# Hocki-IR-Receiver.net
KiCad netlist of a schematic drawn in EAGLE
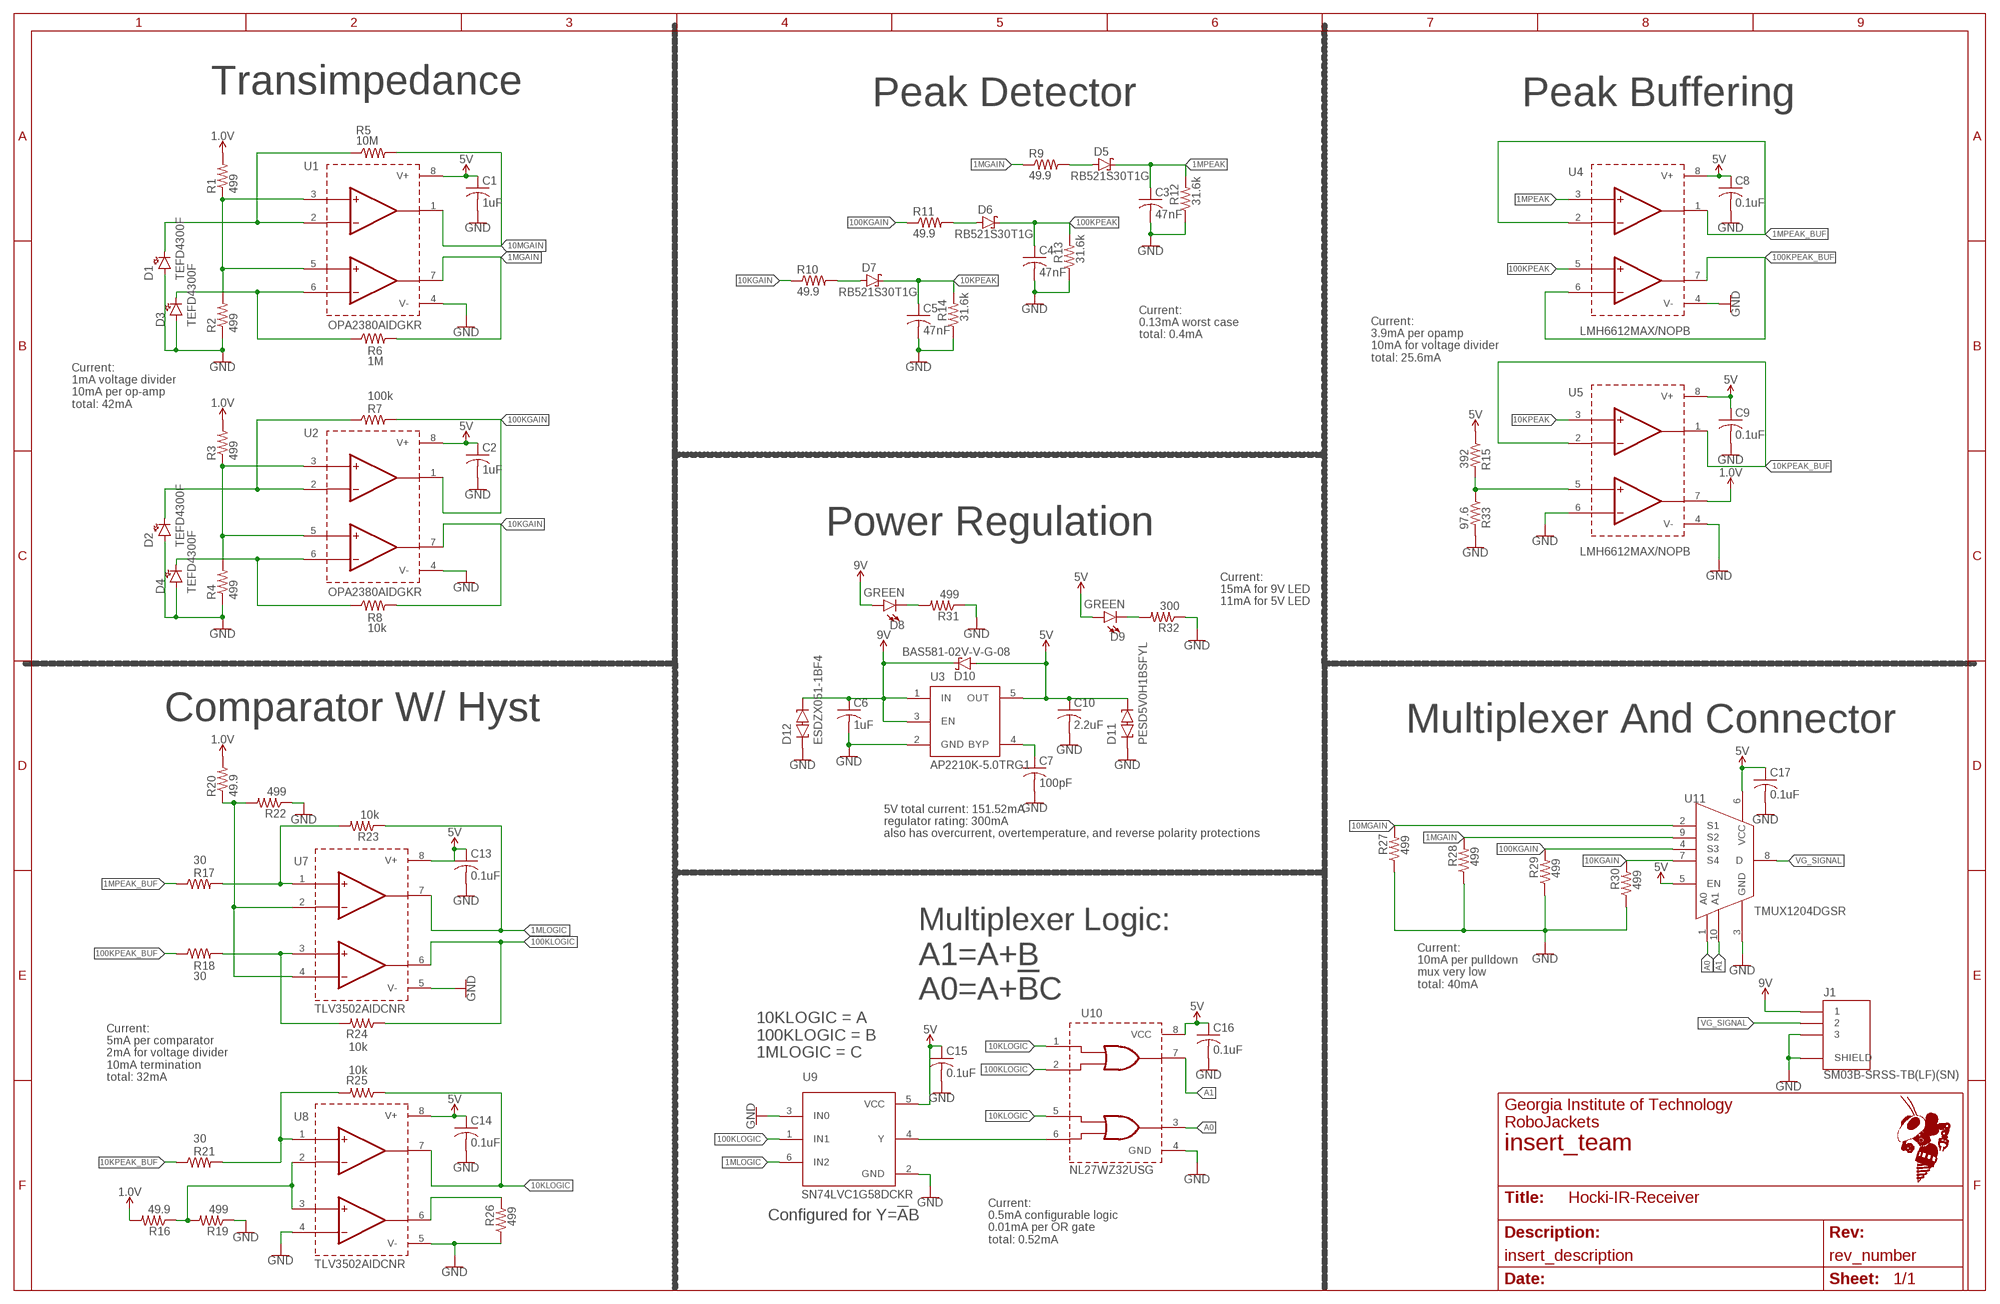
[diagram p0: schematic, sheet 1]

(export (version "E")
  (design (tool "Eeschema 10.0.6"))
  (components
    (comp (ref "C1")
      (value "1uF")
      (footprint "eagle-import:C0603")
      (libsource (lib "eagle-import") (part "C-USC0603"))
    )
    (comp (ref "C2")
      (value "1uF")
      (footprint "eagle-import:C0603")
      (libsource (lib "eagle-import") (part "C-USC0603"))
    )
    (comp (ref "C3")
      (value "47nF")
      (footprint "eagle-import:C1206")
      (libsource (lib "eagle-import") (part "C-USC1206"))
    )
    (comp (ref "C4")
      (value "47nF")
      (footprint "eagle-import:C1206")
      (libsource (lib "eagle-import") (part "C-USC1206"))
    )
    (comp (ref "C5")
      (value "47nF")
      (footprint "eagle-import:C1206")
      (libsource (lib "eagle-import") (part "C-USC1206"))
    )
    (comp (ref "C6")
      (value "1uF")
      (footprint "eagle-import:C0603")
      (libsource (lib "eagle-import") (part "C-USC0603"))
    )
    (comp (ref "C7")
      (value "100pF")
      (footprint "eagle-import:C0603")
      (libsource (lib "eagle-import") (part "C-USC0603"))
    )
    (comp (ref "C8")
      (value "0.1uF")
      (footprint "eagle-import:C0603")
      (libsource (lib "eagle-import") (part "C-USC0603"))
    )
    (comp (ref "C9")
      (value "0.1uF")
      (footprint "eagle-import:C0603")
      (libsource (lib "eagle-import") (part "C-USC0603"))
    )
    (comp (ref "C10")
      (value "2.2uF")
      (footprint "eagle-import:C0603")
      (libsource (lib "eagle-import") (part "C-USC0603"))
    )
    (comp (ref "C13")
      (value "0.1uF")
      (footprint "eagle-import:C0603")
      (libsource (lib "eagle-import") (part "C-USC0603"))
    )
    (comp (ref "C14")
      (value "0.1uF")
      (footprint "eagle-import:C0603")
      (libsource (lib "eagle-import") (part "C-USC0603"))
    )
    (comp (ref "C15")
      (value "0.1uF")
      (footprint "eagle-import:C0603")
      (libsource (lib "eagle-import") (part "C-USC0603"))
    )
    (comp (ref "C16")
      (value "0.1uF")
      (footprint "eagle-import:C0603")
      (libsource (lib "eagle-import") (part "C-USC0603"))
    )
    (comp (ref "C17")
      (value "0.1uF")
      (footprint "eagle-import:C0603")
      (libsource (lib "eagle-import") (part "C-USC0603"))
    )
    (comp (ref "D1")
      (value "TEFD4300F")
      (footprint "eagle-import:TEFD4300F")
      (libsource (lib "eagle-import") (part "TEFD4300F"))
    )
    (comp (ref "D2")
      (value "TEFD4300F")
      (footprint "eagle-import:TEFD4300F")
      (libsource (lib "eagle-import") (part "TEFD4300F"))
    )
    (comp (ref "D3")
      (value "TEFD4300F")
      (footprint "eagle-import:TEFD4300F")
      (libsource (lib "eagle-import") (part "TEFD4300F"))
    )
    (comp (ref "D4")
      (value "TEFD4300F")
      (footprint "eagle-import:TEFD4300F")
      (libsource (lib "eagle-import") (part "TEFD4300F"))
    )
    (comp (ref "D5")
      (value "RB521S30T1G")
      (footprint "eagle-import:SOD-523")
      (libsource (lib "eagle-import") (part "RB521S30T1G"))
    )
    (comp (ref "D6")
      (value "RB521S30T1G")
      (footprint "eagle-import:SOD-523")
      (libsource (lib "eagle-import") (part "RB521S30T1G"))
    )
    (comp (ref "D7")
      (value "RB521S30T1G")
      (footprint "eagle-import:SOD-523")
      (libsource (lib "eagle-import") (part "RB521S30T1G"))
    )
    (comp (ref "D8")
      (value "GREEN")
      (footprint "eagle-import:LED-0603")
      (libsource (lib "eagle-import") (part "LED-GREEN0603"))
    )
    (comp (ref "D9")
      (value "GREEN")
      (footprint "eagle-import:LED-0603")
      (libsource (lib "eagle-import") (part "LED-GREEN0603"))
    )
    (comp (ref "D10")
      (value "BAS581-02V-V-G-08")
      (footprint "eagle-import:SOD-523")
      (libsource (lib "eagle-import") (part "BAS581-02V-V-G-08"))
    )
    (comp (ref "D11")
      (value "PESD5V0H1BSFYL")
      (footprint "eagle-import:DSN0603-2")
      (libsource (lib "eagle-import") (part "PESD5V0H1BSFYL"))
    )
    (comp (ref "D12")
      (value "ESDZX051-1BF4")
      (footprint "eagle-import:DSN0603-2")
      (libsource (lib "eagle-import") (part "ESDZX051-1BF4"))
    )
    (comp (ref "J1")
      (value "SM03B-SRSS-TB(LF)(SN)")
      (footprint "eagle-import:SM03B-SRSS-TB(LF)(SN)")
      (libsource (lib "eagle-import") (part "SM03B-SRSS-TB(LF)(SN)"))
    )
    (comp (ref "R1")
      (value "499")
      (footprint "eagle-import:R0603")
      (libsource (lib "eagle-import") (part "resistor_348_R-US_R0603"))
    )
    (comp (ref "R2")
      (value "499")
      (footprint "eagle-import:R0603")
      (libsource (lib "eagle-import") (part "resistor_348_R-US_R0603"))
    )
    (comp (ref "R3")
      (value "499")
      (footprint "eagle-import:R0603")
      (libsource (lib "eagle-import") (part "resistor_348_R-US_R0603"))
    )
    (comp (ref "R4")
      (value "499")
      (footprint "eagle-import:R0603")
      (libsource (lib "eagle-import") (part "resistor_348_R-US_R0603"))
    )
    (comp (ref "R5")
      (value "10M")
      (footprint "eagle-import:R1206")
      (libsource (lib "eagle-import") (part "R-US_R1206"))
    )
    (comp (ref "R6")
      (value "1M")
      (footprint "eagle-import:R0603")
      (libsource (lib "eagle-import") (part "resistor_348_R-US_R0603"))
    )
    (comp (ref "R7")
      (value "100k")
      (footprint "eagle-import:R0603")
      (libsource (lib "eagle-import") (part "resistor_348_R-US_R0603"))
    )
    (comp (ref "R8")
      (value "10k")
      (footprint "eagle-import:R0603")
      (libsource (lib "eagle-import") (part "resistor_348_R-US_R0603"))
    )
    (comp (ref "R9")
      (value "49.9")
      (footprint "eagle-import:R0603")
      (libsource (lib "eagle-import") (part "resistor_348_R-US_R0603"))
    )
    (comp (ref "R10")
      (value "49.9")
      (footprint "eagle-import:R0603")
      (libsource (lib "eagle-import") (part "resistor_348_R-US_R0603"))
    )
    (comp (ref "R11")
      (value "49.9")
      (footprint "eagle-import:R0603")
      (libsource (lib "eagle-import") (part "resistor_348_R-US_R0603"))
    )
    (comp (ref "R12")
      (value "31.6k")
      (footprint "eagle-import:R0603")
      (libsource (lib "eagle-import") (part "resistor_348_R-US_R0603"))
    )
    (comp (ref "R13")
      (value "31.6k")
      (footprint "eagle-import:R0603")
      (libsource (lib "eagle-import") (part "resistor_348_R-US_R0603"))
    )
    (comp (ref "R14")
      (value "31.6k")
      (footprint "eagle-import:R0603")
      (libsource (lib "eagle-import") (part "resistor_348_R-US_R0603"))
    )
    (comp (ref "R15")
      (value "392")
      (footprint "eagle-import:R0603")
      (libsource (lib "eagle-import") (part "resistor_348_R-US_R0603"))
    )
    (comp (ref "R16")
      (value "49.9")
      (footprint "eagle-import:R0603")
      (libsource (lib "eagle-import") (part "resistor_348_R-US_R0603"))
    )
    (comp (ref "R17")
      (value "30")
      (footprint "eagle-import:R0603")
      (libsource (lib "eagle-import") (part "resistor_348_R-US_R0603"))
    )
    (comp (ref "R18")
      (value "30")
      (footprint "eagle-import:R0603")
      (libsource (lib "eagle-import") (part "resistor_348_R-US_R0603"))
    )
    (comp (ref "R19")
      (value "499")
      (footprint "eagle-import:R0603")
      (libsource (lib "eagle-import") (part "resistor_348_R-US_R0603"))
    )
    (comp (ref "R20")
      (value "49.9")
      (footprint "eagle-import:R0603")
      (libsource (lib "eagle-import") (part "resistor_348_R-US_R0603"))
    )
    (comp (ref "R21")
      (value "30")
      (footprint "eagle-import:R0603")
      (libsource (lib "eagle-import") (part "resistor_348_R-US_R0603"))
    )
    (comp (ref "R22")
      (value "499")
      (footprint "eagle-import:R0603")
      (libsource (lib "eagle-import") (part "resistor_348_R-US_R0603"))
    )
    (comp (ref "R23")
      (value "10k")
      (footprint "eagle-import:R0603")
      (libsource (lib "eagle-import") (part "resistor_348_R-US_R0603"))
    )
    (comp (ref "R24")
      (value "10k")
      (footprint "eagle-import:R0603")
      (libsource (lib "eagle-import") (part "resistor_348_R-US_R0603"))
    )
    (comp (ref "R25")
      (value "10k")
      (footprint "eagle-import:R0603")
      (libsource (lib "eagle-import") (part "resistor_348_R-US_R0603"))
    )
    (comp (ref "R26")
      (value "499")
      (footprint "eagle-import:R0603")
      (libsource (lib "eagle-import") (part "resistor_348_R-US_R0603"))
    )
    (comp (ref "R27")
      (value "499")
      (footprint "eagle-import:R0603")
      (libsource (lib "eagle-import") (part "resistor_348_R-US_R0603"))
    )
    (comp (ref "R28")
      (value "499")
      (footprint "eagle-import:R0603")
      (libsource (lib "eagle-import") (part "resistor_348_R-US_R0603"))
    )
    (comp (ref "R29")
      (value "499")
      (footprint "eagle-import:R0603")
      (libsource (lib "eagle-import") (part "resistor_348_R-US_R0603"))
    )
    (comp (ref "R30")
      (value "499")
      (footprint "eagle-import:R0603")
      (libsource (lib "eagle-import") (part "resistor_348_R-US_R0603"))
    )
    (comp (ref "R31")
      (value "499")
      (footprint "eagle-import:R0603")
      (libsource (lib "eagle-import") (part "resistor_348_R-US_R0603"))
    )
    (comp (ref "R32")
      (value "300")
      (footprint "eagle-import:R0603")
      (libsource (lib "eagle-import") (part "resistor_348_R-US_R0603"))
    )
    (comp (ref "R33")
      (value "97.6")
      (footprint "eagle-import:R0603")
      (libsource (lib "eagle-import") (part "resistor_348_R-US_R0603"))
    )
    (comp (ref "U1")
      (value "OPA2380AIDGKR")
      (footprint "eagle-import:8-VSSOP")
      (libsource (lib "eagle-import") (part "OPA2380AIDGKR"))
    )
    (comp (ref "U2")
      (value "OPA2380AIDGKR")
      (footprint "eagle-import:8-VSSOP")
      (libsource (lib "eagle-import") (part "OPA2380AIDGKR"))
    )
    (comp (ref "U3")
      (value "AP2210K-5.0TRG1")
      (footprint "eagle-import:SOT-23-5")
      (libsource (lib "eagle-import") (part "AP2210K-TRG15.0"))
    )
    (comp (ref "U4")
      (value "LMH6612MAX/NOPB")
      (footprint "eagle-import:8-SOIC")
      (libsource (lib "eagle-import") (part "LMH6612MAX/NOPB"))
    )
    (comp (ref "U5")
      (value "LMH6612MAX/NOPB")
      (footprint "eagle-import:8-SOIC")
      (libsource (lib "eagle-import") (part "LMH6612MAX/NOPB"))
    )
    (comp (ref "U7")
      (value "TLV3502AIDCNR")
      (footprint "eagle-import:SOT-23-8")
      (libsource (lib "eagle-import") (part "TLV3502AIDCNR"))
    )
    (comp (ref "U8")
      (value "TLV3502AIDCNR")
      (footprint "eagle-import:SOT-23-8")
      (libsource (lib "eagle-import") (part "TLV3502AIDCNR"))
    )
    (comp (ref "U9")
      (value "SN74LVC1G58DCKR")
      (footprint "eagle-import:SC-70-6")
      (libsource (lib "eagle-import") (part "SN74LVC1G58DCKR"))
    )
    (comp (ref "U10")
      (value "NL27WZ32USG")
      (footprint "eagle-import:US8")
      (libsource (lib "eagle-import") (part "NL27WZ32USG"))
    )
    (comp (ref "U11")
      (value "TMUX1204DGSR")
      (footprint "eagle-import:10-VSSOP")
      (libsource (lib "eagle-import") (part "TMUX1204DGSR"))
    )
  )
  (nets
    (net (code "1") (name "1.0V") (class "Default")
      (node (ref "R1") (pin "2") (pinfunction "2_2") (pintype "passive"))
      (node (ref "R16") (pin "2") (pinfunction "2_2") (pintype "passive"))
      (node (ref "R20") (pin "2") (pinfunction "2_2") (pintype "passive"))
      (node (ref "R3") (pin "2") (pinfunction "2_2") (pintype "passive"))
      (node (ref "U5") (pin "7") (pinfunction "OUTB_7") (pintype "passive"))
    )
    (net (code "2") (name "1MGAIN") (class "Default")
      (node (ref "R28") (pin "2") (pinfunction "2_2") (pintype "passive"))
      (node (ref "R6") (pin "2") (pinfunction "2_2") (pintype "passive"))
      (node (ref "R9") (pin "1") (pinfunction "1_1") (pintype "passive"))
      (node (ref "U1") (pin "7") (pinfunction "OUTB_7") (pintype "passive"))
      (node (ref "U11") (pin "9") (pinfunction "S2_9") (pintype "passive"))
    )
    (net (code "3") (name "1MLOGIC") (class "Default")
      (node (ref "R23") (pin "1") (pinfunction "1_1") (pintype "passive"))
      (node (ref "U7") (pin "7") (pinfunction "OUTA_7") (pintype "passive"))
      (node (ref "U9") (pin "6") (pinfunction "IN2_6") (pintype "passive"))
    )
    (net (code "4") (name "1MPEAK") (class "Default")
      (node (ref "C3") (pin "1") (pinfunction "1_1") (pintype "passive"))
      (node (ref "D5") (pin "1") (pinfunction "C_1") (pintype "passive"))
      (node (ref "R12") (pin "2") (pinfunction "2_2") (pintype "passive"))
      (node (ref "U4") (pin "3") (pinfunction "INA+_3") (pintype "passive"))
    )
    (net (code "5") (name "1MPEAK_BUF") (class "Default")
      (node (ref "R17") (pin "1") (pinfunction "1_1") (pintype "passive"))
      (node (ref "U4") (pin "1") (pinfunction "OUTA_1") (pintype "passive"))
      (node (ref "U4") (pin "2") (pinfunction "INA-_2") (pintype "passive"))
    )
    (net (code "6") (name "5V") (class "Default")
      (node (ref "C1") (pin "1") (pinfunction "1_1") (pintype "passive"))
      (node (ref "C10") (pin "1") (pinfunction "1_1") (pintype "passive"))
      (node (ref "C13") (pin "1") (pinfunction "1_1") (pintype "passive"))
      (node (ref "C14") (pin "1") (pinfunction "1_1") (pintype "passive"))
      (node (ref "C15") (pin "1") (pinfunction "1_1") (pintype "passive"))
      (node (ref "C16") (pin "1") (pinfunction "1_1") (pintype "passive"))
      (node (ref "C17") (pin "1") (pinfunction "1_1") (pintype "passive"))
      (node (ref "C2") (pin "1") (pinfunction "1_1") (pintype "passive"))
      (node (ref "C8") (pin "1") (pinfunction "1_1") (pintype "passive"))
      (node (ref "C9") (pin "1") (pinfunction "1_1") (pintype "passive"))
      (node (ref "D10") (pin "2") (pinfunction "A_2") (pintype "passive"))
      (node (ref "D11") (pin "C2") (pinfunction "C2_C2") (pintype "passive"))
      (node (ref "D9") (pin "A") (pinfunction "A_A") (pintype "passive"))
      (node (ref "R15") (pin "1") (pinfunction "1_1") (pintype "passive"))
      (node (ref "U1") (pin "8") (pinfunction "V+_8") (pintype "passive"))
      (node (ref "U10") (pin "8") (pinfunction "VCC_8") (pintype "passive"))
      (node (ref "U11") (pin "5") (pinfunction "EN_5") (pintype "passive"))
      (node (ref "U11") (pin "6") (pinfunction "VCC_6") (pintype "passive"))
      (node (ref "U2") (pin "8") (pinfunction "V+_8") (pintype "passive"))
      (node (ref "U3") (pin "5") (pinfunction "OUT_5") (pintype "passive"))
      (node (ref "U4") (pin "8") (pinfunction "V+_8") (pintype "passive"))
      (node (ref "U5") (pin "8") (pinfunction "V+_8") (pintype "passive"))
      (node (ref "U7") (pin "8") (pinfunction "V+_8") (pintype "passive"))
      (node (ref "U8") (pin "8") (pinfunction "V+_8") (pintype "passive"))
      (node (ref "U9") (pin "5") (pinfunction "VCC_5") (pintype "passive"))
    )
    (net (code "7") (name "9V") (class "Default")
      (node (ref "C6") (pin "1") (pinfunction "1_1") (pintype "passive"))
      (node (ref "D10") (pin "1") (pinfunction "C_1") (pintype "passive"))
      (node (ref "D12") (pin "C2") (pinfunction "C2_C2") (pintype "passive"))
      (node (ref "D8") (pin "A") (pinfunction "A_A") (pintype "passive"))
      (node (ref "J1") (pin "1") (pinfunction "1_1") (pintype "passive"))
      (node (ref "U3") (pin "1") (pinfunction "IN_1") (pintype "passive"))
      (node (ref "U3") (pin "3") (pinfunction "EN_3") (pintype "passive"))
    )
    (net (code "8") (name "10KGAIN") (class "Default")
      (node (ref "R10") (pin "1") (pinfunction "1_1") (pintype "passive"))
      (node (ref "R30") (pin "2") (pinfunction "2_2") (pintype "passive"))
      (node (ref "R8") (pin "2") (pinfunction "2_2") (pintype "passive"))
      (node (ref "U11") (pin "7") (pinfunction "S4_7") (pintype "passive"))
      (node (ref "U2") (pin "7") (pinfunction "OUTB_7") (pintype "passive"))
    )
    (net (code "9") (name "10KLOGIC") (class "Default")
      (node (ref "R25") (pin "1") (pinfunction "1_1") (pintype "passive"))
      (node (ref "U10") (pin "1") (pinfunction "A1_1") (pintype "passive"))
      (node (ref "U10") (pin "5") (pinfunction "A2_5") (pintype "passive"))
      (node (ref "U8") (pin "7") (pinfunction "OUTA_7") (pintype "passive"))
    )
    (net (code "10") (name "10KPEAK") (class "Default")
      (node (ref "C5") (pin "1") (pinfunction "1_1") (pintype "passive"))
      (node (ref "D7") (pin "1") (pinfunction "C_1") (pintype "passive"))
      (node (ref "R14") (pin "2") (pinfunction "2_2") (pintype "passive"))
      (node (ref "U5") (pin "3") (pinfunction "INA+_3") (pintype "passive"))
    )
    (net (code "11") (name "10KPEAK_BUF") (class "Default")
      (node (ref "R21") (pin "1") (pinfunction "1_1") (pintype "passive"))
      (node (ref "U5") (pin "1") (pinfunction "OUTA_1") (pintype "passive"))
      (node (ref "U5") (pin "2") (pinfunction "INA-_2") (pintype "passive"))
    )
    (net (code "12") (name "10MGAIN") (class "Default")
      (node (ref "R27") (pin "2") (pinfunction "2_2") (pintype "passive"))
      (node (ref "R5") (pin "2") (pinfunction "2_2") (pintype "passive"))
      (node (ref "U1") (pin "1") (pinfunction "OUTA_1") (pintype "passive"))
      (node (ref "U11") (pin "2") (pinfunction "S1_2") (pintype "passive"))
    )
    (net (code "13") (name "100KGAIN") (class "Default")
      (node (ref "R11") (pin "1") (pinfunction "1_1") (pintype "passive"))
      (node (ref "R29") (pin "2") (pinfunction "2_2") (pintype "passive"))
      (node (ref "R7") (pin "2") (pinfunction "2_2") (pintype "passive"))
      (node (ref "U11") (pin "4") (pinfunction "S3_4") (pintype "passive"))
      (node (ref "U2") (pin "1") (pinfunction "OUTA_1") (pintype "passive"))
    )
    (net (code "14") (name "100KLOGIC") (class "Default")
      (node (ref "R24") (pin "1") (pinfunction "1_1") (pintype "passive"))
      (node (ref "U10") (pin "2") (pinfunction "B1_2") (pintype "passive"))
      (node (ref "U7") (pin "6") (pinfunction "OUTB_6") (pintype "passive"))
      (node (ref "U9") (pin "1") (pinfunction "IN1_1") (pintype "passive"))
    )
    (net (code "15") (name "100KPEAK") (class "Default")
      (node (ref "C4") (pin "1") (pinfunction "1_1") (pintype "passive"))
      (node (ref "D6") (pin "1") (pinfunction "C_1") (pintype "passive"))
      (node (ref "R13") (pin "2") (pinfunction "2_2") (pintype "passive"))
      (node (ref "U4") (pin "5") (pinfunction "INB+_5") (pintype "passive"))
    )
    (net (code "16") (name "100KPEAK_BUF") (class "Default")
      (node (ref "R18") (pin "1") (pinfunction "1_1") (pintype "passive"))
      (node (ref "U4") (pin "6") (pinfunction "INB-_6") (pintype "passive"))
      (node (ref "U4") (pin "7") (pinfunction "OUTB_7") (pintype "passive"))
    )
    (net (code "17") (name "A0") (class "Default")
      (node (ref "U10") (pin "3") (pinfunction "Y2_3") (pintype "passive"))
      (node (ref "U11") (pin "1") (pinfunction "A0_1") (pintype "passive"))
    )
    (net (code "18") (name "A1") (class "Default")
      (node (ref "U10") (pin "7") (pinfunction "Y1_7") (pintype "passive"))
      (node (ref "U11") (pin "10") (pinfunction "A1_10") (pintype "passive"))
    )
    (net (code "19") (name "GND") (class "Default")
      (node (ref "C1") (pin "2") (pinfunction "2_2") (pintype "passive"))
      (node (ref "C10") (pin "2") (pinfunction "2_2") (pintype "passive"))
      (node (ref "C13") (pin "2") (pinfunction "2_2") (pintype "passive"))
      (node (ref "C14") (pin "2") (pinfunction "2_2") (pintype "passive"))
      (node (ref "C15") (pin "2") (pinfunction "2_2") (pintype "passive"))
      (node (ref "C16") (pin "2") (pinfunction "2_2") (pintype "passive"))
      (node (ref "C17") (pin "2") (pinfunction "2_2") (pintype "passive"))
      (node (ref "C2") (pin "2") (pinfunction "2_2") (pintype "passive"))
      (node (ref "C3") (pin "2") (pinfunction "2_2") (pintype "passive"))
      (node (ref "C4") (pin "2") (pinfunction "2_2") (pintype "passive"))
      (node (ref "C5") (pin "2") (pinfunction "2_2") (pintype "passive"))
      (node (ref "C6") (pin "2") (pinfunction "2_2") (pintype "passive"))
      (node (ref "C7") (pin "2") (pinfunction "2_2") (pintype "passive"))
      (node (ref "C8") (pin "2") (pinfunction "2_2") (pintype "passive"))
      (node (ref "C9") (pin "2") (pinfunction "2_2") (pintype "passive"))
      (node (ref "D1") (pin "1") (pinfunction "ANODE_1") (pintype "bidirectional"))
      (node (ref "D11") (pin "C1") (pinfunction "C1_C1") (pintype "passive"))
      (node (ref "D12") (pin "C1") (pinfunction "C1_C1") (pintype "passive"))
      (node (ref "D2") (pin "1") (pinfunction "ANODE_1") (pintype "bidirectional"))
      (node (ref "D3") (pin "1") (pinfunction "ANODE_1") (pintype "bidirectional"))
      (node (ref "D4") (pin "1") (pinfunction "ANODE_1") (pintype "bidirectional"))
      (node (ref "J1") (pin "3") (pinfunction "3_3") (pintype "passive"))
      (node (ref "J1") (pin "S1") (pinfunction "SHIELD_S1") (pintype "passive"))
      (node (ref "J1") (pin "S2") (pinfunction "SHIELD_S2") (pintype "passive"))
      (node (ref "R12") (pin "1") (pinfunction "1_1") (pintype "passive"))
      (node (ref "R13") (pin "1") (pinfunction "1_1") (pintype "passive"))
      (node (ref "R14") (pin "1") (pinfunction "1_1") (pintype "passive"))
      (node (ref "R19") (pin "1") (pinfunction "1_1") (pintype "passive"))
      (node (ref "R2") (pin "1") (pinfunction "1_1") (pintype "passive"))
      (node (ref "R22") (pin "1") (pinfunction "1_1") (pintype "passive"))
      (node (ref "R26") (pin "1") (pinfunction "1_1") (pintype "passive"))
      (node (ref "R27") (pin "1") (pinfunction "1_1") (pintype "passive"))
      (node (ref "R28") (pin "1") (pinfunction "1_1") (pintype "passive"))
      (node (ref "R29") (pin "1") (pinfunction "1_1") (pintype "passive"))
      (node (ref "R30") (pin "1") (pinfunction "1_1") (pintype "passive"))
      (node (ref "R31") (pin "1") (pinfunction "1_1") (pintype "passive"))
      (node (ref "R32") (pin "1") (pinfunction "1_1") (pintype "passive"))
      (node (ref "R33") (pin "2") (pinfunction "2_2") (pintype "passive"))
      (node (ref "R4") (pin "1") (pinfunction "1_1") (pintype "passive"))
      (node (ref "U1") (pin "4") (pinfunction "V-_4") (pintype "passive"))
      (node (ref "U10") (pin "4") (pinfunction "GND_4") (pintype "passive"))
      (node (ref "U11") (pin "3") (pinfunction "GND_3") (pintype "passive"))
      (node (ref "U2") (pin "4") (pinfunction "V-_4") (pintype "passive"))
      (node (ref "U3") (pin "2") (pinfunction "GND_2") (pintype "passive"))
      (node (ref "U4") (pin "4") (pinfunction "V-_4") (pintype "passive"))
      (node (ref "U5") (pin "4") (pinfunction "V-_4") (pintype "passive"))
      (node (ref "U5") (pin "6") (pinfunction "INB-_6") (pintype "passive"))
      (node (ref "U7") (pin "5") (pinfunction "V-_5") (pintype "passive"))
      (node (ref "U8") (pin "4") (pinfunction "INB-_4") (pintype "passive"))
      (node (ref "U8") (pin "5") (pinfunction "V-_5") (pintype "passive"))
      (node (ref "U9") (pin "2") (pinfunction "GND_2") (pintype "passive"))
      (node (ref "U9") (pin "3") (pinfunction "IN0_3") (pintype "passive"))
    )
    (net (code "20") (name "Net-(D1-CATHODE)") (class "Default")
      (node (ref "D1") (pin "2") (pinfunction "CATHODE_2") (pintype "bidirectional"))
      (node (ref "R5") (pin "1") (pinfunction "1_1") (pintype "passive"))
      (node (ref "U1") (pin "2") (pinfunction "INA-_2") (pintype "passive"))
    )
    (net (code "21") (name "Net-(D2-CATHODE)") (class "Default")
      (node (ref "D2") (pin "2") (pinfunction "CATHODE_2") (pintype "bidirectional"))
      (node (ref "R7") (pin "1") (pinfunction "1_1") (pintype "passive"))
      (node (ref "U2") (pin "2") (pinfunction "INA-_2") (pintype "passive"))
    )
    (net (code "22") (name "Net-(D3-CATHODE)") (class "Default")
      (node (ref "D3") (pin "2") (pinfunction "CATHODE_2") (pintype "bidirectional"))
      (node (ref "R6") (pin "1") (pinfunction "1_1") (pintype "passive"))
      (node (ref "U1") (pin "6") (pinfunction "INB-_6") (pintype "passive"))
    )
    (net (code "23") (name "Net-(D4-CATHODE)") (class "Default")
      (node (ref "D4") (pin "2") (pinfunction "CATHODE_2") (pintype "bidirectional"))
      (node (ref "R8") (pin "1") (pinfunction "1_1") (pintype "passive"))
      (node (ref "U2") (pin "6") (pinfunction "INB-_6") (pintype "passive"))
    )
    (net (code "24") (name "Net-(D5-A)") (class "Default")
      (node (ref "D5") (pin "2") (pinfunction "A_2") (pintype "passive"))
      (node (ref "R9") (pin "2") (pinfunction "2_2") (pintype "passive"))
    )
    (net (code "25") (name "Net-(D6-A)") (class "Default")
      (node (ref "D6") (pin "2") (pinfunction "A_2") (pintype "passive"))
      (node (ref "R11") (pin "2") (pinfunction "2_2") (pintype "passive"))
    )
    (net (code "26") (name "Net-(D7-A)") (class "Default")
      (node (ref "D7") (pin "2") (pinfunction "A_2") (pintype "passive"))
      (node (ref "R10") (pin "2") (pinfunction "2_2") (pintype "passive"))
    )
    (net (code "27") (name "Net-(D8-PadC)") (class "Default")
      (node (ref "D8") (pin "C") (pinfunction "C_C") (pintype "passive"))
      (node (ref "R31") (pin "2") (pinfunction "2_2") (pintype "passive"))
    )
    (net (code "28") (name "Net-(D9-PadC)") (class "Default")
      (node (ref "D9") (pin "C") (pinfunction "C_C") (pintype "passive"))
      (node (ref "R32") (pin "2") (pinfunction "2_2") (pintype "passive"))
    )
    (net (code "29") (name "Net-(U1-INA+)") (class "Default")
      (node (ref "R1") (pin "1") (pinfunction "1_1") (pintype "passive"))
      (node (ref "R2") (pin "2") (pinfunction "2_2") (pintype "passive"))
      (node (ref "U1") (pin "3") (pinfunction "INA+_3") (pintype "passive"))
      (node (ref "U1") (pin "5") (pinfunction "INB+_5") (pintype "passive"))
    )
    (net (code "30") (name "Net-(U2-INA+)") (class "Default")
      (node (ref "R3") (pin "1") (pinfunction "1_1") (pintype "passive"))
      (node (ref "R4") (pin "2") (pinfunction "2_2") (pintype "passive"))
      (node (ref "U2") (pin "3") (pinfunction "INA+_3") (pintype "passive"))
      (node (ref "U2") (pin "5") (pinfunction "INB+_5") (pintype "passive"))
    )
    (net (code "31") (name "Net-(U3-BYP)") (class "Default")
      (node (ref "C7") (pin "1") (pinfunction "1_1") (pintype "passive"))
      (node (ref "U3") (pin "4") (pinfunction "BYP_4") (pintype "bidirectional"))
    )
    (net (code "32") (name "Net-(U5-INB+)") (class "Default")
      (node (ref "R15") (pin "2") (pinfunction "2_2") (pintype "passive"))
      (node (ref "R33") (pin "1") (pinfunction "1_1") (pintype "passive"))
      (node (ref "U5") (pin "5") (pinfunction "INB+_5") (pintype "passive"))
    )
    (net (code "33") (name "Net-(U7-INA+)") (class "Default")
      (node (ref "R17") (pin "2") (pinfunction "2_2") (pintype "passive"))
      (node (ref "R23") (pin "2") (pinfunction "2_2") (pintype "passive"))
      (node (ref "U7") (pin "1") (pinfunction "INA+_1") (pintype "passive"))
    )
    (net (code "34") (name "Net-(U7-INA-)") (class "Default")
      (node (ref "R20") (pin "1") (pinfunction "1_1") (pintype "passive"))
      (node (ref "R22") (pin "2") (pinfunction "2_2") (pintype "passive"))
      (node (ref "U7") (pin "2") (pinfunction "INA-_2") (pintype "passive"))
      (node (ref "U7") (pin "4") (pinfunction "INB-_4") (pintype "passive"))
    )
    (net (code "35") (name "Net-(U7-INB+)") (class "Default")
      (node (ref "R18") (pin "2") (pinfunction "2_2") (pintype "passive"))
      (node (ref "R24") (pin "2") (pinfunction "2_2") (pintype "passive"))
      (node (ref "U7") (pin "3") (pinfunction "INB+_3") (pintype "passive"))
    )
    (net (code "36") (name "Net-(U8-INA+)") (class "Default")
      (node (ref "R21") (pin "2") (pinfunction "2_2") (pintype "passive"))
      (node (ref "R25") (pin "2") (pinfunction "2_2") (pintype "passive"))
      (node (ref "U8") (pin "1") (pinfunction "INA+_1") (pintype "passive"))
    )
    (net (code "37") (name "Net-(U8-INA-)") (class "Default")
      (node (ref "R16") (pin "1") (pinfunction "1_1") (pintype "passive"))
      (node (ref "R19") (pin "2") (pinfunction "2_2") (pintype "passive"))
      (node (ref "U8") (pin "2") (pinfunction "INA-_2") (pintype "passive"))
      (node (ref "U8") (pin "3") (pinfunction "INB+_3") (pintype "passive"))
    )
    (net (code "38") (name "Net-(U8-OUTB)") (class "Default")
      (node (ref "R26") (pin "2") (pinfunction "2_2") (pintype "passive"))
      (node (ref "U8") (pin "6") (pinfunction "OUTB_6") (pintype "passive"))
    )
    (net (code "39") (name "Net-(U10-B2)") (class "Default")
      (node (ref "U10") (pin "6") (pinfunction "B2_6") (pintype "passive"))
      (node (ref "U9") (pin "4") (pinfunction "Y_4") (pintype "passive"))
    )
    (net (code "40") (name "VG_SIGNAL") (class "Default")
      (node (ref "J1") (pin "2") (pinfunction "2_2") (pintype "passive"))
      (node (ref "U11") (pin "8") (pinfunction "D_8") (pintype "passive"))
    )
  )
)
